# Moteino.net
KiCad netlist of a schematic drawn in EAGLE
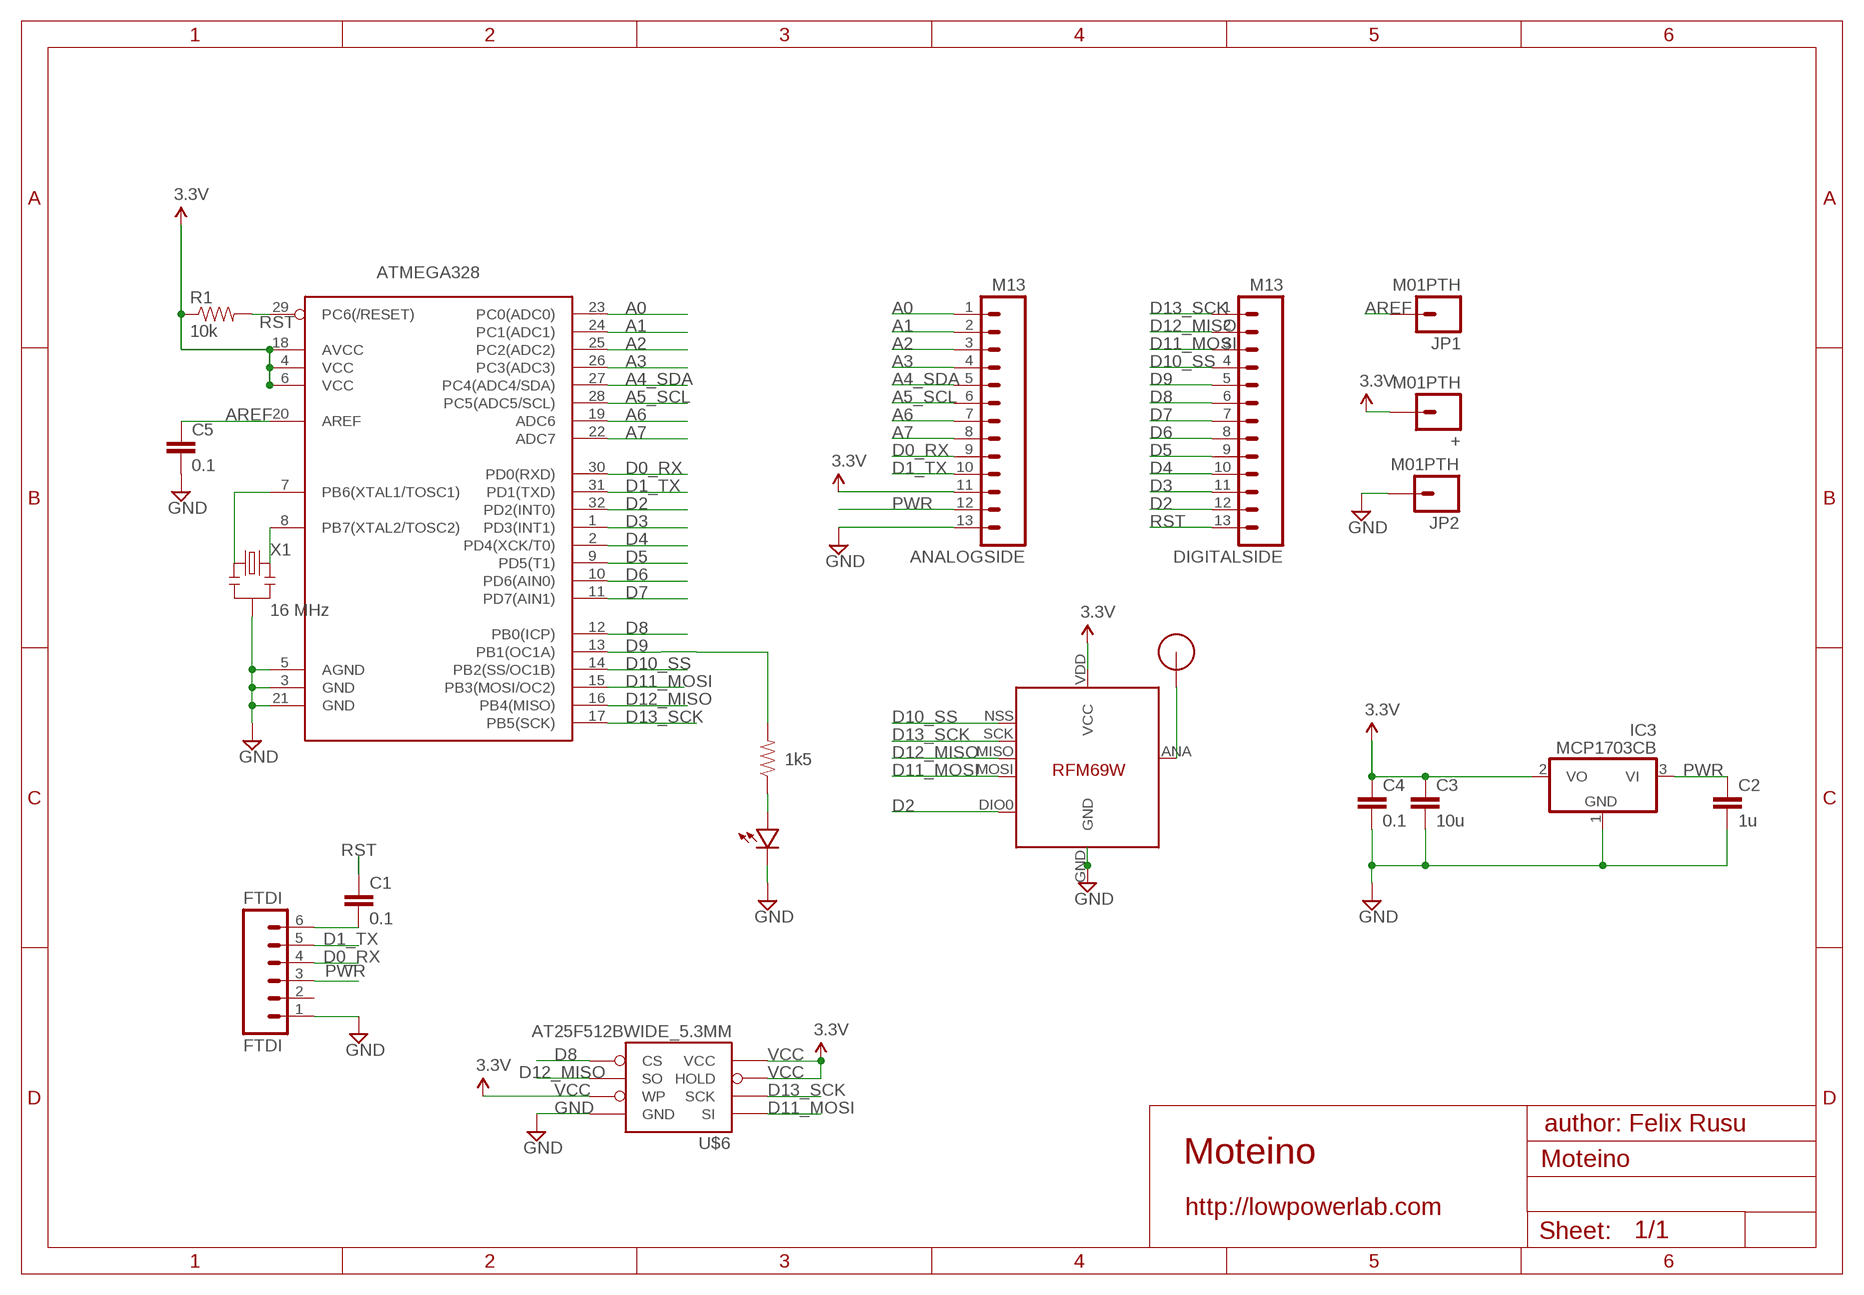
[diagram p0: schematic, sheet 1]

(export (version "E")
  (design (tool "Eeschema 10.0.6"))
  (components
    (comp (ref "+")
      (value "M01PTH")
      (footprint "eagle-import:1X01")
      (libsource (lib "eagle-import") (part "M01PTH"))
    )
    (comp (ref "ANALOGSIDE")
      (value "M13")
      (footprint "eagle-import:1X13")
      (libsource (lib "eagle-import") (part "M13"))
    )
    (comp (ref "ATMEGA328")
      (value "ATMega-328")
      (footprint "eagle-import:TQFP32-08")
      (libsource (lib "eagle-import") (part "ATMEGA168/328TQFP32"))
    )
    (comp (ref "C1")
      (value "0.1")
      (footprint "eagle-import:0603-CAP")
      (libsource (lib "eagle-import") (part "CAP0603-CAP"))
    )
    (comp (ref "C2")
      (value "1u")
      (footprint "eagle-import:0603-CAP")
      (libsource (lib "eagle-import") (part "CAP0603-CAP"))
    )
    (comp (ref "C3")
      (value "10u")
      (footprint "eagle-import:0805-CAP")
      (libsource (lib "eagle-import") (part "CAP0805-CAP"))
    )
    (comp (ref "C4")
      (value "0.1")
      (footprint "eagle-import:0603-CAP")
      (libsource (lib "eagle-import") (part "CAP0603-CAP"))
    )
    (comp (ref "C5")
      (value "0.1")
      (footprint "eagle-import:0603-CAP")
      (libsource (lib "eagle-import") (part "CAP0603-CAP"))
    )
    (comp (ref "DIGITALSIDE")
      (value "M13")
      (footprint "eagle-import:1X13")
      (libsource (lib "eagle-import") (part "M13"))
    )
    (comp (ref "FTDI")
      (value "FTDI")
      (footprint "eagle-import:1X06")
      (libsource (lib "eagle-import") (part "M06SIP"))
    )
    (comp (ref "IC3")
      (value "MCP1703CB")
      (footprint "eagle-import:SOT23")
      (libsource (lib "eagle-import") (part "MCP1703CB"))
    )
    (comp (ref "JP1")
      (value "M01PTH")
      (footprint "eagle-import:1X01")
      (libsource (lib "eagle-import") (part "M01PTH"))
    )
    (comp (ref "JP2")
      (value "M01PTH")
      (footprint "eagle-import:1X01")
      (libsource (lib "eagle-import") (part "M01PTH"))
    )
    (comp (ref "R1")
      (value "10k")
      (footprint "eagle-import:0603-RES")
      (libsource (lib "eagle-import") (part "RESISTOR0603-RES"))
    )
    (comp (ref "R2")
      (value "1k5")
      (footprint "eagle-import:0603-RES")
      (libsource (lib "eagle-import") (part "RESISTOR0603-RES"))
    )
    (comp (ref "U$1")
      (value "RFM12B_ANTENNA")
      (footprint "eagle-import:RFM12B-ANTENNA")
      (libsource (lib "eagle-import") (part "RFM12B_ANTENNA"))
    )
    (comp (ref "U$2")
      (value "LED0603")
      (footprint "eagle-import:0603-LED")
      (libsource (lib "eagle-import") (part "LED0603"))
    )
    (comp (ref "U$5")
      (value "RFM69")
      (footprint "eagle-import:RFM69W-MINPADS")
      (libsource (lib "eagle-import") (part "RFM69"))
    )
    (comp (ref "U$6")
      (value "AT25F512BWIDE_5.3MM")
      (footprint "eagle-import:SO08WIDE")
      (libsource (lib "eagle-import") (part "AT25F512BWIDE_5.3MM"))
    )
    (comp (ref "X1")
      (value "16 MHz")
      (footprint "eagle-import:RESONATOR-SMD")
      (libsource (lib "eagle-import") (part "RESONATORSMD"))
    )
  )
  (nets
    (net (code "1") (name "/A0") (class "Default")
      (node (ref "ANALOGSIDE") (pin "1") (pinfunction "1_1") (pintype "passive"))
      (node (ref "ATMEGA328") (pin "23") (pinfunction "PC0(ADC0)_23") (pintype "bidirectional"))
    )
    (net (code "2") (name "/A1") (class "Default")
      (node (ref "ANALOGSIDE") (pin "2") (pinfunction "2_2") (pintype "passive"))
      (node (ref "ATMEGA328") (pin "24") (pinfunction "PC1(ADC1)_24") (pintype "bidirectional"))
    )
    (net (code "3") (name "/A2") (class "Default")
      (node (ref "ANALOGSIDE") (pin "3") (pinfunction "3_3") (pintype "passive"))
      (node (ref "ATMEGA328") (pin "25") (pinfunction "PC2(ADC2)_25") (pintype "bidirectional"))
    )
    (net (code "4") (name "/A3") (class "Default")
      (node (ref "ANALOGSIDE") (pin "4") (pinfunction "4_4") (pintype "passive"))
      (node (ref "ATMEGA328") (pin "26") (pinfunction "PC3(ADC3)_26") (pintype "bidirectional"))
    )
    (net (code "5") (name "/A4_SDA") (class "Default")
      (node (ref "ANALOGSIDE") (pin "5") (pinfunction "5_5") (pintype "passive"))
      (node (ref "ATMEGA328") (pin "27") (pinfunction "PC4(ADC4/SDA)_27") (pintype "bidirectional"))
    )
    (net (code "6") (name "/A5_SCL") (class "Default")
      (node (ref "ANALOGSIDE") (pin "6") (pinfunction "6_6") (pintype "passive"))
      (node (ref "ATMEGA328") (pin "28") (pinfunction "PC5(ADC5/SCL)_28") (pintype "bidirectional"))
    )
    (net (code "7") (name "/A6") (class "Default")
      (node (ref "ANALOGSIDE") (pin "7") (pinfunction "7_7") (pintype "passive"))
      (node (ref "ATMEGA328") (pin "19") (pinfunction "ADC6_19") (pintype "bidirectional"))
    )
    (net (code "8") (name "/A7") (class "Default")
      (node (ref "ANALOGSIDE") (pin "8") (pinfunction "8_8") (pintype "passive"))
      (node (ref "ATMEGA328") (pin "22") (pinfunction "ADC7_22") (pintype "bidirectional"))
    )
    (net (code "9") (name "/AREF") (class "Default")
      (node (ref "ATMEGA328") (pin "20") (pinfunction "AREF_20") (pintype "bidirectional"))
      (node (ref "C5") (pin "1") (pinfunction "1_1") (pintype "passive"))
      (node (ref "JP1") (pin "1") (pinfunction "1_1") (pintype "passive"))
    )
    (net (code "10") (name "/D0_RX") (class "Default")
      (node (ref "ANALOGSIDE") (pin "9") (pinfunction "9_9") (pintype "passive"))
      (node (ref "ATMEGA328") (pin "30") (pinfunction "PD0(RXD)_30") (pintype "bidirectional"))
      (node (ref "FTDI") (pin "4") (pinfunction "4_4") (pintype "passive"))
    )
    (net (code "11") (name "/D1_TX") (class "Default")
      (node (ref "ANALOGSIDE") (pin "10") (pinfunction "10_10") (pintype "passive"))
      (node (ref "ATMEGA328") (pin "31") (pinfunction "PD1(TXD)_31") (pintype "bidirectional"))
      (node (ref "FTDI") (pin "5") (pinfunction "5_5") (pintype "passive"))
    )
    (net (code "12") (name "/D2") (class "Default")
      (node (ref "ATMEGA328") (pin "32") (pinfunction "PD2(INT0)_32") (pintype "bidirectional"))
      (node (ref "DIGITALSIDE") (pin "12") (pinfunction "12_12") (pintype "passive"))
      (node (ref "U$5") (pin "DIO0") (pinfunction "DIO0_DIO0") (pintype "open_collector"))
    )
    (net (code "13") (name "/D3") (class "Default")
      (node (ref "ATMEGA328") (pin "1") (pinfunction "PD3(INT1)_1") (pintype "bidirectional"))
      (node (ref "DIGITALSIDE") (pin "11") (pinfunction "11_11") (pintype "passive"))
    )
    (net (code "14") (name "/D4") (class "Default")
      (node (ref "ATMEGA328") (pin "2") (pinfunction "PD4(XCK/T0)_2") (pintype "bidirectional"))
      (node (ref "DIGITALSIDE") (pin "10") (pinfunction "10_10") (pintype "passive"))
    )
    (net (code "15") (name "/D5") (class "Default")
      (node (ref "ATMEGA328") (pin "9") (pinfunction "PD5(T1)_9") (pintype "bidirectional"))
      (node (ref "DIGITALSIDE") (pin "9") (pinfunction "9_9") (pintype "passive"))
    )
    (net (code "16") (name "/D6") (class "Default")
      (node (ref "ATMEGA328") (pin "10") (pinfunction "PD6(AIN0)_10") (pintype "bidirectional"))
      (node (ref "DIGITALSIDE") (pin "8") (pinfunction "8_8") (pintype "passive"))
    )
    (net (code "17") (name "/D7") (class "Default")
      (node (ref "ATMEGA328") (pin "11") (pinfunction "PD7(AIN1)_11") (pintype "bidirectional"))
      (node (ref "DIGITALSIDE") (pin "7") (pinfunction "7_7") (pintype "passive"))
    )
    (net (code "18") (name "/D8") (class "Default")
      (node (ref "ATMEGA328") (pin "12") (pinfunction "PB0(ICP)_12") (pintype "bidirectional"))
      (node (ref "DIGITALSIDE") (pin "6") (pinfunction "6_6") (pintype "passive"))
      (node (ref "U$6") (pin "1") (pinfunction "CS_1") (pintype "bidirectional"))
    )
    (net (code "19") (name "/D9") (class "Default")
      (node (ref "ATMEGA328") (pin "13") (pinfunction "PB1(OC1A)_13") (pintype "bidirectional"))
      (node (ref "DIGITALSIDE") (pin "5") (pinfunction "5_5") (pintype "passive"))
      (node (ref "R2") (pin "2") (pinfunction "2_2") (pintype "passive"))
    )
    (net (code "20") (name "/D10_SS") (class "Default")
      (node (ref "ATMEGA328") (pin "14") (pinfunction "PB2(SS/OC1B)_14") (pintype "bidirectional"))
      (node (ref "DIGITALSIDE") (pin "4") (pinfunction "4_4") (pintype "passive"))
      (node (ref "U$5") (pin "NSS") (pinfunction "SEL_NSS") (pintype "input"))
    )
    (net (code "21") (name "/D11_MOSI") (class "Default")
      (node (ref "ATMEGA328") (pin "15") (pinfunction "PB3(MOSI/OC2)_15") (pintype "bidirectional"))
      (node (ref "DIGITALSIDE") (pin "3") (pinfunction "3_3") (pintype "passive"))
      (node (ref "U$5") (pin "MOSI") (pinfunction "MOSI_MOSI") (pintype "output"))
      (node (ref "U$6") (pin "5") (pinfunction "SI_5") (pintype "bidirectional"))
    )
    (net (code "22") (name "/D12_MISO") (class "Default")
      (node (ref "ATMEGA328") (pin "16") (pinfunction "PB4(MISO)_16") (pintype "bidirectional"))
      (node (ref "DIGITALSIDE") (pin "2") (pinfunction "2_2") (pintype "passive"))
      (node (ref "U$5") (pin "MISO") (pinfunction "MISO_MISO") (pintype "input"))
      (node (ref "U$6") (pin "2") (pinfunction "SO_2") (pintype "bidirectional"))
    )
    (net (code "23") (name "/D13_SCK") (class "Default")
      (node (ref "ATMEGA328") (pin "17") (pinfunction "PB5(SCK)_17") (pintype "bidirectional"))
      (node (ref "DIGITALSIDE") (pin "1") (pinfunction "1_1") (pintype "passive"))
      (node (ref "U$5") (pin "SCK") (pinfunction "SCK_SCK") (pintype "input"))
      (node (ref "U$6") (pin "6") (pinfunction "SCK_6") (pintype "bidirectional"))
    )
    (net (code "24") (name "/PWR") (class "Default")
      (node (ref "ANALOGSIDE") (pin "12") (pinfunction "12_12") (pintype "passive"))
      (node (ref "C2") (pin "1") (pinfunction "1_1") (pintype "passive"))
      (node (ref "FTDI") (pin "3") (pinfunction "3_3") (pintype "passive"))
      (node (ref "IC3") (pin "3") (pinfunction "VI_3") (pintype "input"))
    )
    (net (code "25") (name "/RST") (class "Default")
      (node (ref "ATMEGA328") (pin "29") (pinfunction "PC6(/RESET)_29") (pintype "bidirectional"))
      (node (ref "C1") (pin "1") (pinfunction "1_1") (pintype "passive"))
      (node (ref "DIGITALSIDE") (pin "13") (pinfunction "13_13") (pintype "passive"))
      (node (ref "R1") (pin "2") (pinfunction "2_2") (pintype "passive"))
    )
    (net (code "26") (name "3.3V") (class "Default")
      (node (ref "+") (pin "1") (pinfunction "1_1") (pintype "passive"))
      (node (ref "ANALOGSIDE") (pin "11") (pinfunction "11_11") (pintype "passive"))
      (node (ref "ATMEGA328") (pin "18") (pinfunction "AVCC_18") (pintype "bidirectional"))
      (node (ref "ATMEGA328") (pin "4") (pinfunction "VCC_4") (pintype "bidirectional"))
      (node (ref "ATMEGA328") (pin "6") (pinfunction "VCC_6") (pintype "bidirectional"))
      (node (ref "C3") (pin "1") (pinfunction "1_1") (pintype "passive"))
      (node (ref "C4") (pin "1") (pinfunction "1_1") (pintype "passive"))
      (node (ref "IC3") (pin "2") (pinfunction "VO_2") (pintype "passive"))
      (node (ref "R1") (pin "1") (pinfunction "1_1") (pintype "passive"))
      (node (ref "U$5") (pin "VDD") (pinfunction "VCC_VDD") (pintype "power_in"))
      (node (ref "U$6") (pin "3") (pinfunction "WP_3") (pintype "bidirectional"))
      (node (ref "U$6") (pin "7") (pinfunction "HOLD_7") (pintype "bidirectional"))
      (node (ref "U$6") (pin "8") (pinfunction "VCC_8") (pintype "bidirectional"))
    )
    (net (code "27") (name "GND") (class "Default")
      (node (ref "ANALOGSIDE") (pin "13") (pinfunction "13_13") (pintype "passive"))
      (node (ref "ATMEGA328") (pin "21") (pinfunction "GND_21") (pintype "bidirectional"))
      (node (ref "ATMEGA328") (pin "3") (pinfunction "GND_3") (pintype "bidirectional"))
      (node (ref "ATMEGA328") (pin "5") (pinfunction "AGND_5") (pintype "bidirectional"))
      (node (ref "C2") (pin "2") (pinfunction "2_2") (pintype "passive"))
      (node (ref "C3") (pin "2") (pinfunction "2_2") (pintype "passive"))
      (node (ref "C4") (pin "2") (pinfunction "2_2") (pintype "passive"))
      (node (ref "C5") (pin "2") (pinfunction "2_2") (pintype "passive"))
      (node (ref "FTDI") (pin "1") (pinfunction "1_1") (pintype "passive"))
      (node (ref "IC3") (pin "1") (pinfunction "GND_1") (pintype "passive"))
      (node (ref "JP2") (pin "1") (pinfunction "1_1") (pintype "passive"))
      (node (ref "U$2") (pin "MINUS") (pinfunction "MINUS_MINUS") (pintype "passive"))
      (node (ref "U$5") (pin "GND") (pinfunction "GND_GND") (pintype "power_in"))
      (node (ref "U$6") (pin "4") (pinfunction "GND_4") (pintype "bidirectional"))
      (node (ref "X1") (pin "2") (pinfunction "2_2") (pintype "passive"))
    )
    (net (code "28") (name "Net-(ATMEGA328-PB6(XTAL1{slash}TOSC1))") (class "Default")
      (node (ref "ATMEGA328") (pin "7") (pinfunction "PB6(XTAL1/TOSC1)_7") (pintype "bidirectional"))
      (node (ref "X1") (pin "1") (pinfunction "1_1") (pintype "passive"))
    )
    (net (code "29") (name "Net-(ATMEGA328-PB7(XTAL2{slash}TOSC2))") (class "Default")
      (node (ref "ATMEGA328") (pin "8") (pinfunction "PB7(XTAL2/TOSC2)_8") (pintype "bidirectional"))
      (node (ref "X1") (pin "3") (pinfunction "3_3") (pintype "passive"))
    )
    (net (code "30") (name "Net-(C1-Pad2)") (class "Default")
      (node (ref "C1") (pin "2") (pinfunction "2_2") (pintype "passive"))
      (node (ref "FTDI") (pin "6") (pinfunction "6_6") (pintype "passive"))
    )
    (net (code "31") (name "Net-(R2-Pad1)") (class "Default")
      (node (ref "R2") (pin "1") (pinfunction "1_1") (pintype "passive"))
      (node (ref "U$2") (pin "PLUS") (pinfunction "PLUS_PLUS") (pintype "passive"))
    )
    (net (code "32") (name "Net-(U$1-1)") (class "Default")
      (node (ref "U$1") (pin "P$1") (pinfunction "1_P$1") (pintype "bidirectional"))
      (node (ref "U$5") (pin "ANA") (pinfunction "ANT_ANA") (pintype "passive"))
    )
    (net (code "33") (name "unconnected-(FTDI-Pad2)") (class "Default")
      (node (ref "FTDI") (pin "2") (pinfunction "2_2") (pintype "passive"))
    )
  )
)
